# Sheet2.net
KiCad netlist of a schematic drawn in Altium Designer
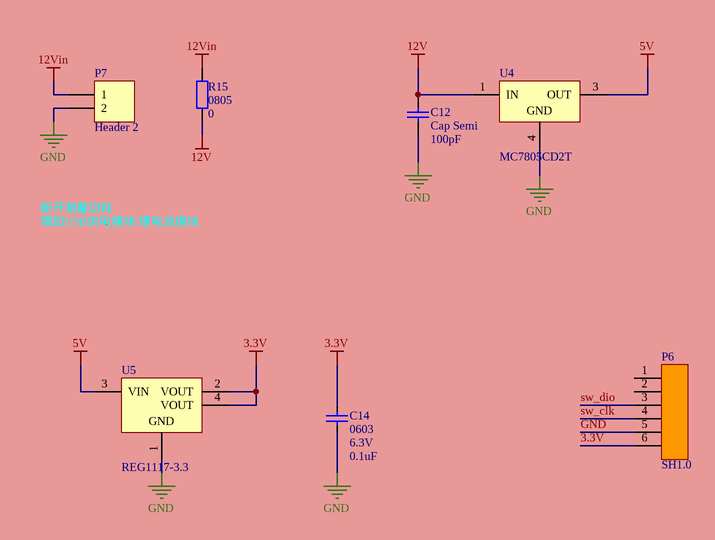
[diagram p0: Sheet2.SchDoc]

(export (version "E")
  (design (tool "Eeschema 10.0.6"))
  (components
    (comp (ref "C12")
      (value "Cap Semi")
      (footprint "C1206")
      (description "Capacitor (Semiconductor SIM Model)")
      (fields (field (name "ALTIUM_VALUE") "100pF") (field (name "PUBLISHER") "Altium Limited"))
      (libsource (lib "Miscellaneous Devices") (part "Cap Semi"))
    )
    (comp (ref "C14")
      (value "0.1uF")
      (footprint "0603")
      (description "Capacitor 0603")
      (fields (field (name "VOLTAGE") "6.3V") (field (name "Comment") "CAP_0603"))
      (libsource (lib "Charles_Schlib") (part "CAP_0603"))
    )
    (comp (ref "P6")
      (value "SH1.0")
      (footprint "SH1.0_6_PIN")
      (description "1.0mm connector")
      (libsource (lib "Charles_Schlib") (part "SH1.0_6_PIN"))
    )
    (comp (ref "P7")
      (value "Header 2")
      (footprint "HDR1X2")
      (description "Header, 2-Pin")
      (fields (field (name "PUBLISHER") "Altium Limited"))
      (libsource (lib "Miscellaneous Connectors") (part "Header 2"))
    )
    (comp (ref "R15")
      (value "0")
      (footprint "0805")
      (description "Resister")
      (fields (field (name "Comment") "RES_0805"))
      (libsource (lib "Charles_Schlib") (part "RES_0805"))
    )
    (comp (ref "U4")
      (value "MC7805CD2T")
      (footprint "936-03")
      (description "Three-Terminal Positive Voltage Regulator")
      (fields (field (name "PUBLISHER") "Altium Limited"))
      (libsource (lib "ON Semi Power Mgt Voltage Regulator") (part "MC7805CD2T"))
    )
    (comp (ref "U5")
      (value "REG1117-3.3")
      (footprint "TI-DCY4_N")
      (fields (field (name "MANUFACTURER") "Texas Instruments"))
      (libsource (lib "TI Power Management Linear Regulator Single Channel LDO (400-7500mA)") (part "REG1117-3.3"))
    )
  )
  (nets
    (net (code "1") (name "/sw_clk") (class "Default") (node (ref "P6") (pin "4") (pintype "passive")))
    (net (code "2") (name "/sw_dio") (class "Default") (node (ref "P6") (pin "3") (pintype "passive")))
    (net (code "3") (name "3.3V") (class "Default")
      (node (ref "C14") (pin "2") (pinfunction "2_2") (pintype "passive"))
      (node (ref "P6") (pin "6") (pintype "passive"))
      (node (ref "U5") (pin "2") (pinfunction "VOUT_2") (pintype "power_in"))
      (node (ref "U5") (pin "4") (pinfunction "VOUT_4") (pintype "power_in"))
    )
    (net (code "4") (name "5V") (class "Default")
      (node (ref "U4") (pin "3") (pinfunction "OUT_3") (pintype "power_in"))
      (node (ref "U5") (pin "3") (pinfunction "VIN_3") (pintype "power_in"))
    )
    (net (code "5") (name "12V") (class "Default")
      (node (ref "C12") (pin "1") (pinfunction "1_1") (pintype "passive"))
      (node (ref "R15") (pin "1") (pinfunction "1_1") (pintype "passive"))
      (node (ref "U4") (pin "1") (pinfunction "IN_1") (pintype "power_in"))
    )
    (net (code "6") (name "12Vin") (class "Default")
      (node (ref "P7") (pin "1") (pinfunction "1_1") (pintype "passive"))
      (node (ref "R15") (pin "2") (pinfunction "2_2") (pintype "passive"))
    )
    (net (code "7") (name "GND") (class "Default")
      (node (ref "C12") (pin "2") (pinfunction "2_2") (pintype "passive"))
      (node (ref "C14") (pin "1") (pinfunction "1_1") (pintype "passive"))
      (node (ref "P6") (pin "5") (pintype "passive"))
      (node (ref "P7") (pin "2") (pinfunction "2_2") (pintype "passive"))
      (node (ref "U4") (pin "4") (pinfunction "GND_4") (pintype "power_in"))
      (node (ref "U5") (pin "1") (pinfunction "GND_1") (pintype "power_in"))
    )
    (net (code "8") (name "unconnected-(P6-Pad1)") (class "Default")
      (node (ref "P6") (pin "1") (pintype "passive"))
    )
    (net (code "9") (name "unconnected-(P6-Pad2)") (class "Default")
      (node (ref "P6") (pin "2") (pintype "passive"))
    )
  )
)
